# ADC_PowerSupply.net
KiCad netlist of a schematic drawn in Altium Designer
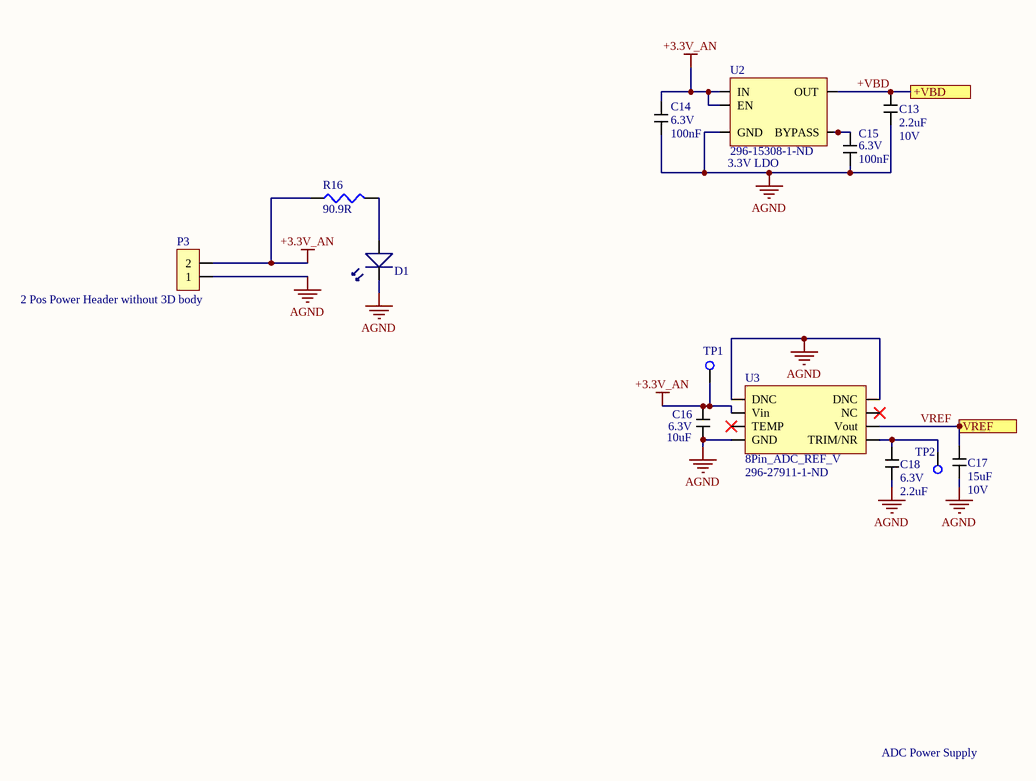
[diagram p0: ADC_PowerSupply.SchDoc]

(export (version "E")
  (design (tool "Eeschema 10.0.6"))
  (components
    (comp (ref "C13")
      (value "2.2uF LDO Bypass Cap")
      (footprint "2.2uF LDO Output Bypass Cap")
      (description "2.2µF ±10% 10V Ceramic Capacitor X7R 0805 (2012 Metric)")
      (fields
        (field (name "MANUFACTURER") "KEMET")
        (field (name "MANUFACTURER PART NUMBER") "C0805C225K8RACAUTO")
        (field (name "CAPACITANCE") "2.2uF")
        (field (name "VOLTAGE RATING") "10V")
      )
      (libsource (lib "Schematic_Library") (part "2.2uF LDO Bypass Cap"))
    )
    (comp (ref "C14")
      (value "0.1uF")
      (footprint "0.1uF Bypass Capacitor")
      (description "0.1uF Bypass Cap")
      (fields
        (field (name "MANUFACTURER") "KEMET")
        (field (name "MANUFACTURER PART NUMBER") "C0603C104K9RACTU")
        (field (name "VOLTAGE RATING") "6.3V")
        (field (name "CAPACITANCE") "100nF")
      )
      (libsource (lib "Schematic_Library") (part "0.1uF Cap"))
    )
    (comp (ref "C15")
      (value "0.1uF")
      (footprint "0.1uF Bypass Capacitor")
      (description "0.1uF Bypass Cap")
      (fields
        (field (name "MANUFACTURER") "KEMET")
        (field (name "MANUFACTURER PART NUMBER") "C0603C104K9RACTU")
        (field (name "VOLTAGE RATING") "6.3V")
        (field (name "CAPACITANCE") "100nF")
      )
      (libsource (lib "Schematic_Library") (part "0.1uF Cap"))
    )
    (comp (ref "C16")
      (value "ADC_Volt_Ref_Input_Bypass_CAP10uF")
      (footprint "0805_MD_CAP")
      (description "10µF ±10% 6.3V Ceramic Capacitor X7R 0805 (2012 Metric)")
      (fields
        (field (name "MANUFACTURER") "Taiyo Yuden")
        (field (name "MANUFACTURER PART NUMBER") "JMK212AB7106KGHT")
        (field (name "VOLTAGE RATING") "6.3V")
        (field (name "CAPACITANCE") "10uF")
      )
      (libsource (lib "Schematic_Library") (part "ADC_Volt_Ref_Input_Bypass_CAP10uF"))
    )
    (comp (ref "C17")
      (value "ADC_REF_VOLT_OUTPUT_CAP15UF")
      (footprint "1206_MD_CAP_Width_MOD")
      (description "15µF Molded Tantalum Capacitors 10V 1206 (3216 Metric) 1Ohm")
      (fields
        (field (name "MANUFACTURER") "Kyocera AVX")
        (field (name "MANUFACTURER PART NUMBER") "TPSA156K010R1000")
        (field (name "CAPACITANCE") "15uF")
        (field (name "VOLTAGE RATING") "10V")
      )
      (libsource (lib "Schematic_Library") (part "ADC_REF_VOLT_OUTPUT_CAP15UF"))
    )
    (comp (ref "C18")
      (value "ADC_REF_VOLT_TRIM_CAP2.2UF")
      (footprint "0603_MD_CAP")
      (description "2.2µF ±10% 6.3V Ceramic Capacitor X7R 0603 (1608 Metric)")
      (fields
        (field (name "MANUFACTURER") "Taiyo Yuden")
        (field (name "MANUFACTURER PART NUMBER") "JMK107B7225KAHTR")
        (field (name "VOLTAGE RATING") "6.3V")
        (field (name "CAPACITANCE") "2.2uF")
      )
      (libsource (lib "Schematic_Library") (part "ADC_REF_VOLT_TRIM_CAP2.2UF"))
    )
    (comp (ref "D1")
      (value "LED")
      (footprint "Green_SMD_LED")
      (fields
        (field (name "MANUFACTURER") "Dialight")
        (field (name "MANUFACTURER PART NUMBER") "5988070107F")
      )
      (libsource (lib "Schematic_Library") (part "GREEN_LED"))
    )
    (comp (ref "P3")
      (value "2 Pos Power Header without 3D body")
      (footprint "2 Pos Power Header - duplicate")
      (libsource (lib "Schematic_Library") (part "2 Pos Power Header without 3D body"))
    )
    (comp (ref "R16")
      (value "Green")
      (footprint "Green_LED_Resistor_90.9")
      (fields
        (field (name "MANUFACTURER") "Panasonic")
        (field (name "MANUFACTURER PART NUMBER") "ERJ-1GNF90R9C")
        (field (name "TOLERANCE") "1%")
        (field (name "RESISTANCE") "90.9R")
      )
      (libsource (lib "Schematic_Library") (part "Green_LED_Res"))
    )
    (comp (ref "TP1")
      (value "Test Point")
      (footprint "Test Point")
      (libsource (lib "Schematic_Library") (part "Test Point"))
    )
    (comp (ref "TP2")
      (value "Test Point")
      (footprint "Test Point")
      (libsource (lib "Schematic_Library") (part "Test Point"))
    )
    (comp (ref "U2")
      (value "3.3V Digital ADC Supply")
      (footprint "3.3V Dig ADC Supply")
      (description "Linear Voltage Regulator IC  1 Output  200mA SOT-23-5")
      (fields
        (field (name "MANUFACTURER") "Texas Instruments")
        (field (name "MANUFACTURER PART NUMBER") "TPS79333DBVRQ1")
        (field (name "SUPPLIER PART NUMBER 1") "296-15308-1-ND")
      )
      (libsource (lib "Schematic_Library") (part "3.3V Digital ADC Supply"))
    )
    (comp (ref "U3")
      (value "8Pin_ADC_REF_V")
      (footprint "SOIC127P600X175-8N")
      (fields
        (field (name "MANUFACTURER") "Texas Instruments")
        (field (name "MANUFACTURER PART NUMBER") "REF5025AQDRQ1")
        (field (name "TOLERANCE") "0.1%")
        (field (name "SUPPLIER PART NUMBER 1") "296-27911-1-ND")
      )
      (libsource (lib "Schematic_Library") (part "8Pin_ADC_REF_V"))
    )
  )
  (nets
    (net (code "1") (name "+3.3V_AN") (class "Default")
      (node (ref "C14") (pin "2") (pinfunction "2_2") (pintype "passive"))
      (node (ref "C16") (pin "2") (pinfunction "2_2") (pintype "passive"))
      (node (ref "P3") (pin "2") (pinfunction "2_2") (pintype "passive"))
      (node (ref "R16") (pin "1") (pinfunction "1_1") (pintype "passive"))
      (node (ref "TP1") (pin "1") (pinfunction "1_1") (pintype "passive"))
      (node (ref "U2") (pin "1") (pinfunction "IN_1") (pintype "passive"))
      (node (ref "U2") (pin "3") (pinfunction "EN_3") (pintype "passive"))
      (node (ref "U3") (pin "2") (pinfunction "Vin_2") (pintype "passive"))
    )
    (net (code "2") (name "/+VBD") (class "Default")
      (node (ref "C13") (pin "2") (pinfunction "2_2") (pintype "passive"))
      (node (ref "U2") (pin "5") (pinfunction "OUT_5") (pintype "passive"))
    )
    (net (code "3") (name "/VREF") (class "Default")
      (node (ref "C17") (pin "2") (pinfunction "2_2") (pintype "passive"))
      (node (ref "U3") (pin "6") (pinfunction "Vout_6") (pintype "passive"))
    )
    (net (code "4") (name "AGND") (class "Default")
      (node (ref "C13") (pin "1") (pinfunction "1_1") (pintype "passive"))
      (node (ref "C14") (pin "1") (pinfunction "1_1") (pintype "passive"))
      (node (ref "C15") (pin "1") (pinfunction "1_1") (pintype "passive"))
      (node (ref "C16") (pin "1") (pinfunction "1_1") (pintype "passive"))
      (node (ref "C17") (pin "1") (pinfunction "1_1") (pintype "passive"))
      (node (ref "C18") (pin "1") (pinfunction "1_1") (pintype "passive"))
      (node (ref "D1") (pin "1") (pinfunction "1_1") (pintype "passive"))
      (node (ref "P3") (pin "1") (pinfunction "1_1") (pintype "passive"))
      (node (ref "U2") (pin "2") (pinfunction "GND_2") (pintype "passive"))
      (node (ref "U3") (pin "1") (pinfunction "DNC_1") (pintype "passive"))
      (node (ref "U3") (pin "4") (pinfunction "GND_4") (pintype "passive"))
      (node (ref "U3") (pin "8") (pinfunction "DNC_8") (pintype "passive"))
    )
    (net (code "5") (name "Net-(D1-Pad2)") (class "Default")
      (node (ref "D1") (pin "2") (pinfunction "2_2") (pintype "passive"))
      (node (ref "R16") (pin "2") (pinfunction "2_2") (pintype "passive"))
    )
    (net (code "6") (name "Net-(U2-BYPASS)") (class "Default")
      (node (ref "C15") (pin "2") (pinfunction "2_2") (pintype "passive"))
      (node (ref "U2") (pin "4") (pinfunction "BYPASS_4") (pintype "passive"))
    )
    (net (code "7") (name "Net-(U3-TRIM{slash}NR)") (class "Default")
      (node (ref "C18") (pin "2") (pinfunction "2_2") (pintype "passive"))
      (node (ref "TP2") (pin "1") (pinfunction "1_1") (pintype "passive"))
      (node (ref "U3") (pin "5") (pinfunction "TRIM/NR_5") (pintype "passive"))
    )
    (net (code "8") (name "unconnected-(U3-NC-Pad7)") (class "Default")
      (node (ref "U3") (pin "7") (pinfunction "NC_7") (pintype "passive+no_connect"))
    )
    (net (code "9") (name "unconnected-(U3-TEMP-Pad3)") (class "Default")
      (node (ref "U3") (pin "3") (pinfunction "TEMP_3") (pintype "passive+no_connect"))
    )
  )
)
